# PWM_Input_Filter.net
KiCad netlist of a schematic drawn in EAGLE
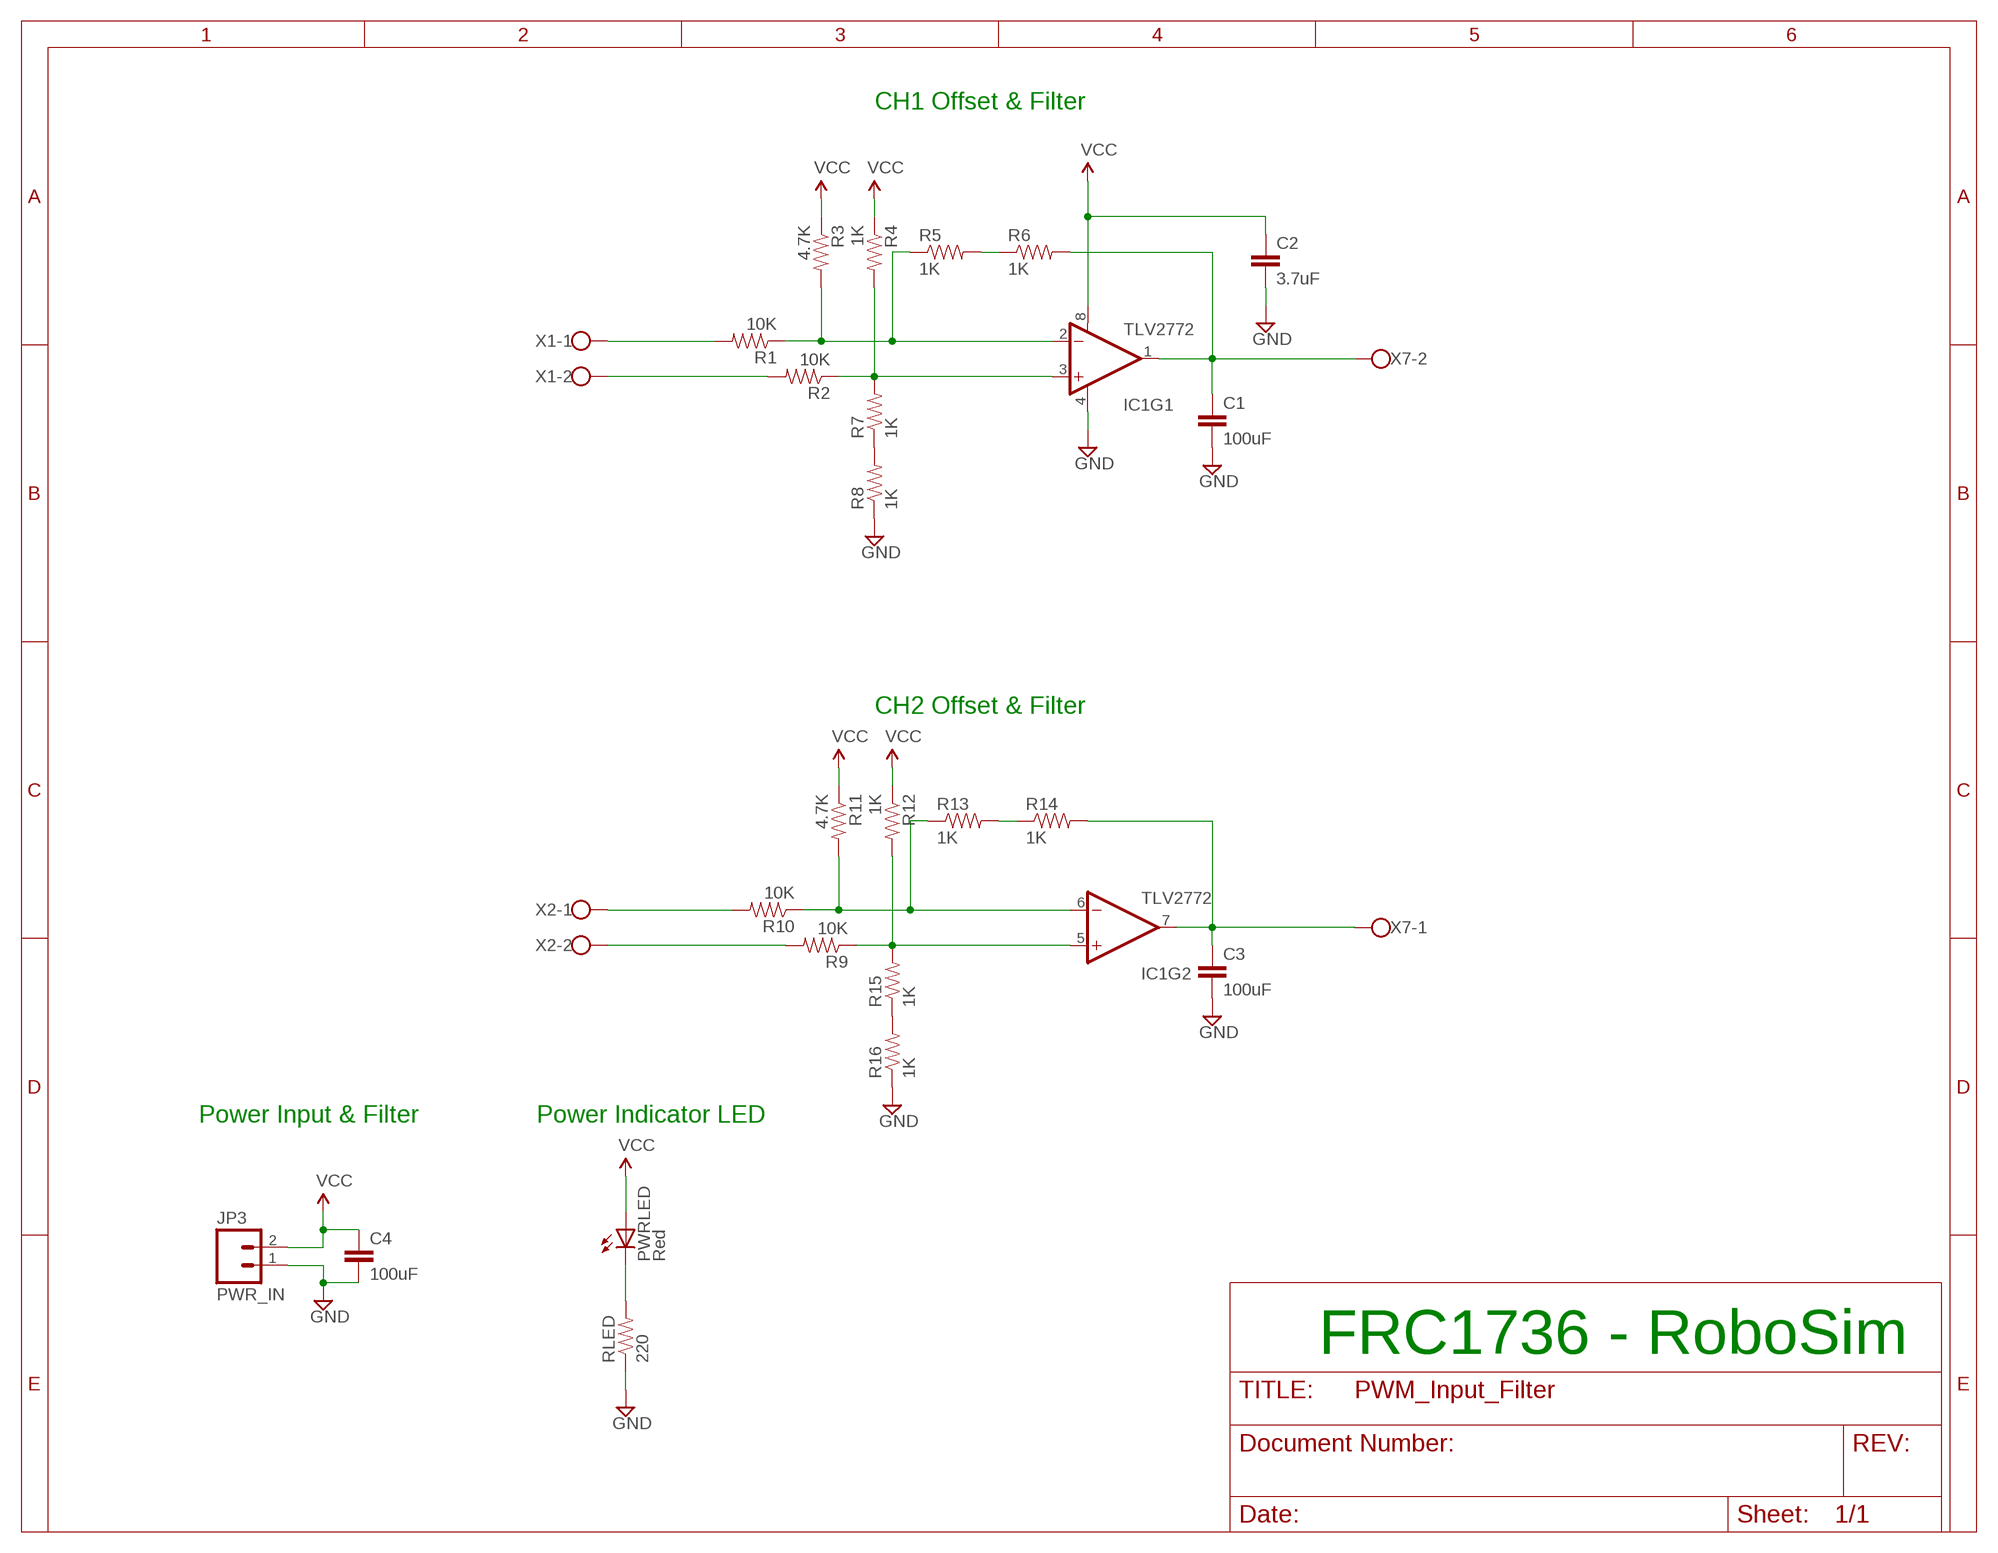
[diagram p0: schematic, sheet 1]

(export (version "E")
  (design (tool "Eeschema 10.0.6"))
  (components
    (comp (ref "C1")
      (value "100uF")
      (footprint "eagle-import:CAP-PTH-SMALL")
      (libsource (lib "eagle-import") (part "CAPPTH"))
    )
    (comp (ref "C2")
      (value "3.7uF")
      (footprint "eagle-import:CAP-PTH-SMALL")
      (libsource (lib "eagle-import") (part "CAPPTH"))
    )
    (comp (ref "C3")
      (value "100uF")
      (footprint "eagle-import:CAP-PTH-SMALL")
      (libsource (lib "eagle-import") (part "CAPPTH"))
    )
    (comp (ref "C4")
      (value "100uF")
      (footprint "eagle-import:CAP-PTH-SMALL")
      (libsource (lib "eagle-import") (part "CAPPTH"))
    )
    (comp (ref "IC1")
      (value "TLV2772")
      (footprint "eagle-import:DIP08")
      (libsource (lib "eagle-import") (part "LM358"))
    )
    (comp (ref "JP3")
      (value "PWR_IN")
      (footprint "eagle-import:1X02_LOCK")
      (libsource (lib "eagle-import") (part "M02LOCK"))
    )
    (comp (ref "PWRLED")
      (value "Red")
      (footprint "eagle-import:LED5MM")
      (libsource (lib "eagle-import") (part "LED5MM"))
    )
    (comp (ref "R1")
      (value "10K")
      (footprint "eagle-import:AXIAL-0.3")
      (libsource (lib "eagle-import") (part "RESISTORAXIAL-0.3"))
    )
    (comp (ref "R2")
      (value "10K")
      (footprint "eagle-import:AXIAL-0.3")
      (libsource (lib "eagle-import") (part "RESISTORAXIAL-0.3"))
    )
    (comp (ref "R3")
      (value "4.7K")
      (footprint "eagle-import:AXIAL-0.3")
      (libsource (lib "eagle-import") (part "RESISTORAXIAL-0.3"))
    )
    (comp (ref "R4")
      (value "1K")
      (footprint "eagle-import:AXIAL-0.3")
      (libsource (lib "eagle-import") (part "RESISTORAXIAL-0.3"))
    )
    (comp (ref "R5")
      (value "1K")
      (footprint "eagle-import:AXIAL-0.3")
      (libsource (lib "eagle-import") (part "RESISTORAXIAL-0.3"))
    )
    (comp (ref "R6")
      (value "1K")
      (footprint "eagle-import:AXIAL-0.3")
      (libsource (lib "eagle-import") (part "RESISTORAXIAL-0.3"))
    )
    (comp (ref "R7")
      (value "1K")
      (footprint "eagle-import:AXIAL-0.3")
      (libsource (lib "eagle-import") (part "RESISTORAXIAL-0.3"))
    )
    (comp (ref "R8")
      (value "1K")
      (footprint "eagle-import:AXIAL-0.3")
      (libsource (lib "eagle-import") (part "RESISTORAXIAL-0.3"))
    )
    (comp (ref "R9")
      (value "10K")
      (footprint "eagle-import:AXIAL-0.3")
      (libsource (lib "eagle-import") (part "RESISTORAXIAL-0.3"))
    )
    (comp (ref "R10")
      (value "10K")
      (footprint "eagle-import:AXIAL-0.3")
      (libsource (lib "eagle-import") (part "RESISTORAXIAL-0.3"))
    )
    (comp (ref "R11")
      (value "4.7K")
      (footprint "eagle-import:AXIAL-0.3")
      (libsource (lib "eagle-import") (part "RESISTORAXIAL-0.3"))
    )
    (comp (ref "R12")
      (value "1K")
      (footprint "eagle-import:AXIAL-0.3")
      (libsource (lib "eagle-import") (part "RESISTORAXIAL-0.3"))
    )
    (comp (ref "R13")
      (value "1K")
      (footprint "eagle-import:AXIAL-0.3")
      (libsource (lib "eagle-import") (part "RESISTORAXIAL-0.3"))
    )
    (comp (ref "R14")
      (value "1K")
      (footprint "eagle-import:AXIAL-0.3")
      (libsource (lib "eagle-import") (part "RESISTORAXIAL-0.3"))
    )
    (comp (ref "R15")
      (value "1K")
      (footprint "eagle-import:AXIAL-0.3")
      (libsource (lib "eagle-import") (part "RESISTORAXIAL-0.3"))
    )
    (comp (ref "R16")
      (value "1K")
      (footprint "eagle-import:AXIAL-0.3")
      (libsource (lib "eagle-import") (part "RESISTORAXIAL-0.3"))
    )
    (comp (ref "RLED")
      (value "220")
      (footprint "eagle-import:AXIAL-0.3")
      (libsource (lib "eagle-import") (part "RESISTORAXIAL-0.3"))
    )
    (comp (ref "X1")
      (value "W237-102")
      (footprint "eagle-import:W237-102")
      (fields (field (name "MPN") "237-102"))
      (libsource (lib "eagle-import") (part "W237-102"))
    )
    (comp (ref "X2")
      (value "W237-102")
      (footprint "eagle-import:W237-102")
      (fields (field (name "MPN") "237-102"))
      (libsource (lib "eagle-import") (part "W237-102"))
    )
    (comp (ref "X7")
      (value "W237-102")
      (footprint "eagle-import:W237-102")
      (fields (field (name "MPN") "237-102"))
      (libsource (lib "eagle-import") (part "W237-102"))
    )
  )
  (nets
    (net (code "1") (name "GND") (class "Default")
      (node (ref "C1") (pin "2") (pinfunction "2_2") (pintype "passive"))
      (node (ref "C2") (pin "2") (pinfunction "2_2") (pintype "passive"))
      (node (ref "C3") (pin "2") (pinfunction "2_2") (pintype "passive"))
      (node (ref "C4") (pin "2") (pinfunction "2_2") (pintype "passive"))
      (node (ref "IC1") (pin "4") (pinfunction "V-_4") (pintype "power_in"))
      (node (ref "JP3") (pin "1") (pinfunction "1_1") (pintype "passive"))
      (node (ref "R16") (pin "P$1") (pinfunction "1_P$1") (pintype "passive"))
      (node (ref "R8") (pin "P$1") (pinfunction "1_P$1") (pintype "passive"))
      (node (ref "RLED") (pin "P$1") (pinfunction "1_P$1") (pintype "passive"))
    )
    (net (code "2") (name "Net-(IC1A-+IN)") (class "Default")
      (node (ref "IC1") (pin "3") (pinfunction "+IN_3") (pintype "input"))
      (node (ref "R2") (pin "P$1") (pinfunction "1_P$1") (pintype "passive"))
      (node (ref "R4") (pin "P$2") (pinfunction "2_P$2") (pintype "passive"))
      (node (ref "R7") (pin "P$2") (pinfunction "2_P$2") (pintype "passive"))
    )
    (net (code "3") (name "Net-(IC1A--IN)") (class "Default")
      (node (ref "IC1") (pin "2") (pinfunction "-IN_2") (pintype "input"))
      (node (ref "R1") (pin "P$1") (pinfunction "1_P$1") (pintype "passive"))
      (node (ref "R3") (pin "P$2") (pinfunction "2_P$2") (pintype "passive"))
      (node (ref "R5") (pin "P$1") (pinfunction "1_P$1") (pintype "passive"))
    )
    (net (code "4") (name "Net-(IC1A-OUT)") (class "Default")
      (node (ref "C1") (pin "1") (pinfunction "1_1") (pintype "passive"))
      (node (ref "IC1") (pin "1") (pinfunction "OUT_1") (pintype "output"))
      (node (ref "R6") (pin "P$2") (pinfunction "2_P$2") (pintype "passive"))
      (node (ref "X7") (pin "2") (pinfunction "KL_2") (pintype "passive"))
    )
    (net (code "5") (name "Net-(IC1B-+IN)") (class "Default")
      (node (ref "IC1") (pin "5") (pinfunction "+IN_5") (pintype "input"))
      (node (ref "R12") (pin "P$2") (pinfunction "2_P$2") (pintype "passive"))
      (node (ref "R15") (pin "P$2") (pinfunction "2_P$2") (pintype "passive"))
      (node (ref "R9") (pin "P$1") (pinfunction "1_P$1") (pintype "passive"))
    )
    (net (code "6") (name "Net-(IC1B--IN)") (class "Default")
      (node (ref "IC1") (pin "6") (pinfunction "-IN_6") (pintype "input"))
      (node (ref "R10") (pin "P$1") (pinfunction "1_P$1") (pintype "passive"))
      (node (ref "R11") (pin "P$2") (pinfunction "2_P$2") (pintype "passive"))
      (node (ref "R13") (pin "P$1") (pinfunction "1_P$1") (pintype "passive"))
    )
    (net (code "7") (name "Net-(IC1B-OUT)") (class "Default")
      (node (ref "C3") (pin "1") (pinfunction "1_1") (pintype "passive"))
      (node (ref "IC1") (pin "7") (pinfunction "OUT_7") (pintype "output"))
      (node (ref "R14") (pin "P$2") (pinfunction "2_P$2") (pintype "passive"))
      (node (ref "X7") (pin "1") (pinfunction "KL_1") (pintype "passive"))
    )
    (net (code "8") (name "Net-(PWRLED-C)") (class "Default")
      (node (ref "PWRLED") (pin "K") (pinfunction "C_K") (pintype "passive"))
      (node (ref "RLED") (pin "P$2") (pinfunction "2_P$2") (pintype "passive"))
    )
    (net (code "9") (name "Net-(R1-2)") (class "Default")
      (node (ref "R1") (pin "P$2") (pinfunction "2_P$2") (pintype "passive"))
      (node (ref "X1") (pin "1") (pinfunction "KL_1") (pintype "passive"))
    )
    (net (code "10") (name "Net-(R2-2)") (class "Default")
      (node (ref "R2") (pin "P$2") (pinfunction "2_P$2") (pintype "passive"))
      (node (ref "X1") (pin "2") (pinfunction "KL_2") (pintype "passive"))
    )
    (net (code "11") (name "Net-(R5-2)") (class "Default")
      (node (ref "R5") (pin "P$2") (pinfunction "2_P$2") (pintype "passive"))
      (node (ref "R6") (pin "P$1") (pinfunction "1_P$1") (pintype "passive"))
    )
    (net (code "12") (name "Net-(R7-1)") (class "Default")
      (node (ref "R7") (pin "P$1") (pinfunction "1_P$1") (pintype "passive"))
      (node (ref "R8") (pin "P$2") (pinfunction "2_P$2") (pintype "passive"))
    )
    (net (code "13") (name "Net-(R9-2)") (class "Default")
      (node (ref "R9") (pin "P$2") (pinfunction "2_P$2") (pintype "passive"))
      (node (ref "X2") (pin "2") (pinfunction "KL_2") (pintype "passive"))
    )
    (net (code "14") (name "Net-(R10-2)") (class "Default")
      (node (ref "R10") (pin "P$2") (pinfunction "2_P$2") (pintype "passive"))
      (node (ref "X2") (pin "1") (pinfunction "KL_1") (pintype "passive"))
    )
    (net (code "15") (name "Net-(R13-2)") (class "Default")
      (node (ref "R13") (pin "P$2") (pinfunction "2_P$2") (pintype "passive"))
      (node (ref "R14") (pin "P$1") (pinfunction "1_P$1") (pintype "passive"))
    )
    (net (code "16") (name "Net-(R15-1)") (class "Default")
      (node (ref "R15") (pin "P$1") (pinfunction "1_P$1") (pintype "passive"))
      (node (ref "R16") (pin "P$2") (pinfunction "2_P$2") (pintype "passive"))
    )
    (net (code "17") (name "VCC") (class "Default")
      (node (ref "C2") (pin "1") (pinfunction "1_1") (pintype "passive"))
      (node (ref "C4") (pin "1") (pinfunction "1_1") (pintype "passive"))
      (node (ref "IC1") (pin "8") (pinfunction "V+_8") (pintype "power_in"))
      (node (ref "JP3") (pin "2") (pinfunction "2_2") (pintype "passive"))
      (node (ref "PWRLED") (pin "A") (pinfunction "A_A") (pintype "passive"))
      (node (ref "R11") (pin "P$1") (pinfunction "1_P$1") (pintype "passive"))
      (node (ref "R12") (pin "P$1") (pinfunction "1_P$1") (pintype "passive"))
      (node (ref "R3") (pin "P$1") (pinfunction "1_P$1") (pintype "passive"))
      (node (ref "R4") (pin "P$1") (pinfunction "1_P$1") (pintype "passive"))
    )
  )
)
